# Regulators.net
KiCad netlist of a schematic drawn in Altium Designer
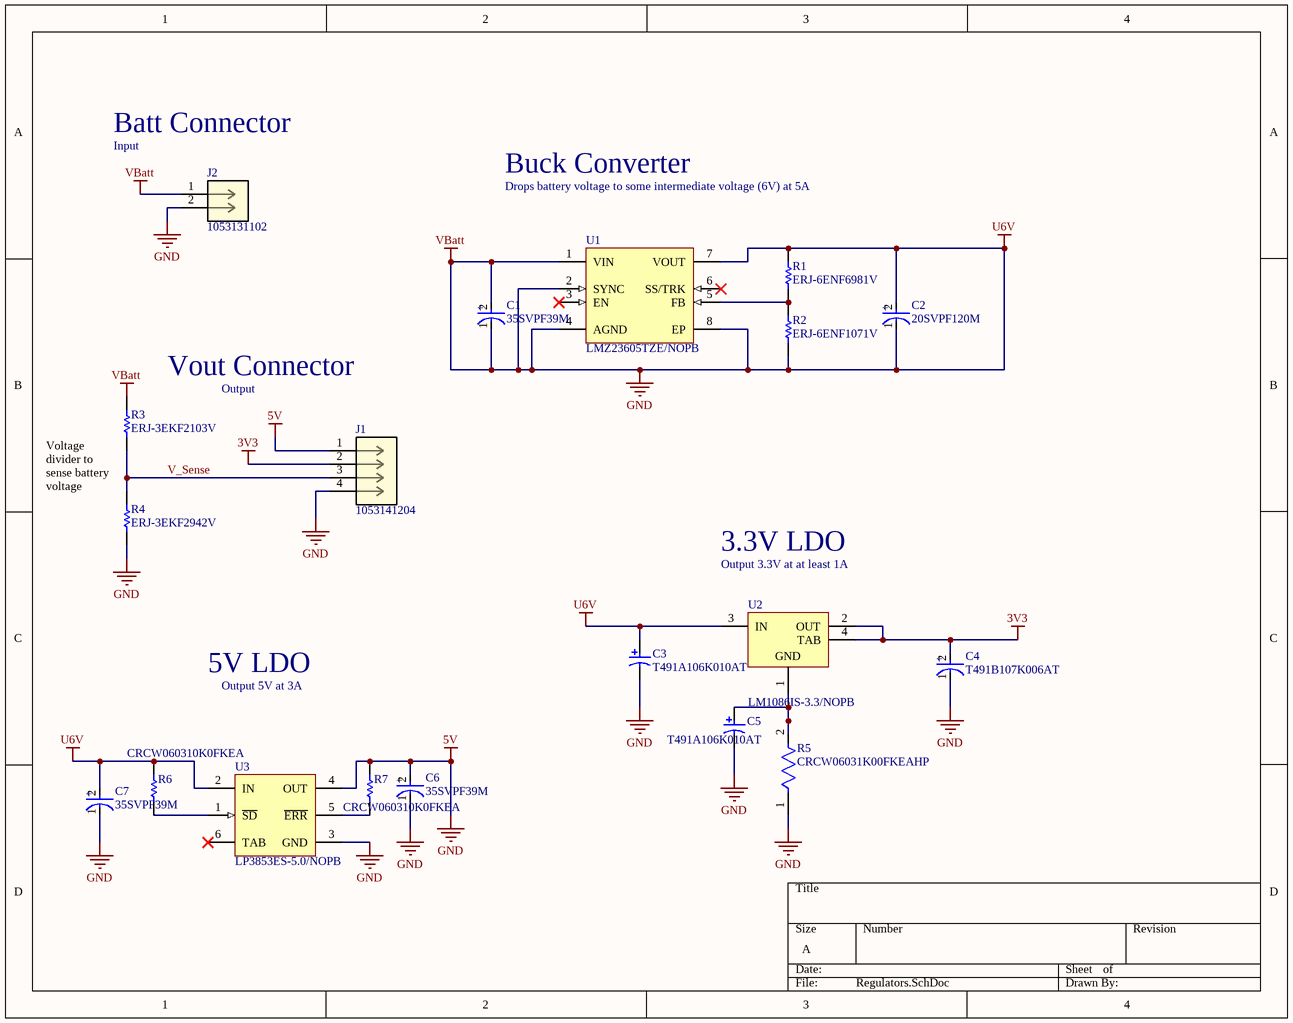
[diagram p0: Regulators.SchDoc]

(export (version "E")
  (design (tool "Eeschema 10.0.6"))
  (components
    (comp (ref "C1")
      (value "35SVPF39M")
      (footprint "FP-OS-CON-SMT-E7-MFG")
      (description "Conductive Polymer Aluminum Solid Capacitors (OS-CON) 39uF ±20% 35V RADIAL SMT 8x6.9mm")
      (fields (field (name "TOLERANCE") "20%") (field (name "VOLTAGE") "35V"))
      (libsource (lib "39uF Buck") (part "CMP-05428-001379-1"))
    )
    (comp (ref "C2")
      (value "20SVPF120M")
      (footprint "FP-OS-CON-SMT-C6-MFG")
      (description "Conductive Polymer Aluminum Solid Capacitors (OS-CON) 120uF ±20% 20V")
      (fields (field (name "TOLERANCE") "20%") (field (name "VOLTAGE") "20V"))
      (libsource (lib "120uF Buck") (part "CMP-05428-001333-1"))
    )
    (comp (ref "C3")
      (value "T491A106K010AT")
      (footprint "KEMT-A-3216-18-2_M")
      (description "Capacitor, Tantalum, 10 uF, +/- 10%, 10 V, -55 to 125 degC, 2-Pin SMD (1206), RoHS, Tape and Reel")
      (fields (field (name "TOLERANCE") "±10%") (field (name "MANUFACTURER") "Kemet"))
      (libsource (lib "10uF 3V3LDO") (part "CMP-2000-05172-1"))
    )
    (comp (ref "C4")
      (value "T491B107K006AT")
      (footprint "FP-T491B107K006AT-MFG")
      (description "CAP TANT 100UF 10% 6.3V 1411")
      (fields (field (name "VOLTAGE") "6.3V") (field (name "TOLERANCE") "10%"))
      (libsource (lib "100uF 3V3LDO") (part "CMP-03017-000031-1"))
    )
    (comp (ref "C5")
      (value "T491A106K010AT")
      (footprint "KEMT-A-3216-18-2_M")
      (description "Capacitor, Tantalum, 10 uF, +/- 10%, 10 V, -55 to 125 degC, 2-Pin SMD (1206), RoHS, Tape and Reel")
      (fields (field (name "TOLERANCE") "±10%") (field (name "MANUFACTURER") "Kemet"))
      (libsource (lib "10uF 3V3LDO") (part "CMP-2000-05172-1"))
    )
    (comp (ref "C6")
      (value "35SVPF39M")
      (footprint "FP-OS-CON-SMT-E7-MFG")
      (description "Conductive Polymer Aluminum Solid Capacitors (OS-CON) 39uF ±20% 35V RADIAL SMT 8x6.9mm")
      (fields (field (name "TOLERANCE") "20%") (field (name "VOLTAGE") "35V"))
      (libsource (lib "39uF Buck") (part "CMP-05428-001379-1"))
    )
    (comp (ref "C7")
      (value "35SVPF39M")
      (footprint "FP-OS-CON-SMT-E7-MFG")
      (description "Conductive Polymer Aluminum Solid Capacitors (OS-CON) 39uF ±20% 35V RADIAL SMT 8x6.9mm")
      (fields (field (name "TOLERANCE") "20%") (field (name "VOLTAGE") "35V"))
      (libsource (lib "39uF Buck") (part "CMP-05428-001379-1"))
    )
    (comp (ref "J1")
      (value "1053141204")
      (footprint "CON_1053141204")
      (description "No Description Available")
      (fields (field (name "COPYRIGHT") "Copyright (C) 2022 Ultra Librarian. All rights reserved."))
      (libsource (lib "tvc_lib_sch") (part "1053141204"))
    )
    (comp (ref "J2")
      (value "1053131102")
      (footprint "CON_1053131102")
      (description "No Description Available")
      (fields (field (name "COPYRIGHT") "Copyright (C) 2022 Ultra Librarian. All rights reserved."))
      (libsource (lib "tvc_lib_sch") (part "1053131102"))
    )
    (comp (ref "R1")
      (value "ERJ-6ENF6981V")
      (footprint "RESC2013X70X40NL20T20")
      (fields (field (name "MANUFACTURER") "Panasonic"))
      (libsource (lib "6.98kR Buck") (part "CMP-2001-00277-1"))
    )
    (comp (ref "R2")
      (value "ERJ-6ENF1071V")
      (footprint "RESC2013X70X40NL20T20")
      (fields (field (name "MANUFACTURER") "Panasonic"))
      (libsource (lib "1.07kR Buck") (part "CMP-2001-04388-1"))
    )
    (comp (ref "R3")
      (value "ERJ-3EKF2103V")
      (footprint "RESC1608X55X30NL15T15")
      (fields (field (name "MANUFACTURER") "Panasonic"))
      (libsource (lib "210kR VD") (part "CMP-2000-00329-1"))
    )
    (comp (ref "R4")
      (value "ERJ-3EKF2942V")
      (footprint "RESC1608X55X30NL15T15")
      (fields (field (name "MANUFACTURER") "Panasonic"))
      (libsource (lib "29.4kR VD") (part "CMP-2000-00409-1"))
    )
    (comp (ref "R5")
      (value "CRCW06031K00FKEAHP")
      (footprint "FP-CRCW0603-HPe3-IPC_B")
      (description "RES Thick Film, 1kΩ, 1%, 0.33W, 100ppm/°C, 0603")
      (fields (field (name "TOLERANCE") "1%"))
      (libsource (lib "1kR 3v3LDO") (part "CMP-2000-02970-2"))
    )
    (comp (ref "R6")
      (value "CRCW060310K0FKEA")
      (footprint "RESC1609X50X30LL8T20")
      (description "Chip Resistor, 10 KOhm, +/- 1%, 100 mW, -55 to 155 degC, 0603 (1608 Metric), RoHS, Tape and Reel")
      (fields (field (name "MANUFACTURER") "Vishay Semiconductor"))
      (libsource (lib "10kR 5LDO") (part "CMP-1666-00005-4"))
    )
    (comp (ref "R7")
      (value "CRCW060310K0FKEA")
      (footprint "RESC1609X50X30LL8T20")
      (description "Chip Resistor, 10 KOhm, +/- 1%, 100 mW, -55 to 155 degC, 0603 (1608 Metric), RoHS, Tape and Reel")
      (fields (field (name "MANUFACTURER") "Vishay Semiconductor"))
      (libsource (lib "10kR 5LDO") (part "CMP-1666-00005-4"))
    )
    (comp (ref "U1")
      (value "LMZ23605TZE/NOPB")
      (footprint "NDW0007A_V")
      (description "5A SIMPLE SWITCHER® Power Module with 36V Maximum Input Voltage, 7 pin TO-PMOD, 250 Reel")
      (fields (field (name "MANUFACTURER") "Texas Instruments"))
      (libsource (lib "25Vto6V 5A Buck") (part "CMP-0069-02071-2"))
    )
    (comp (ref "U2")
      (value "LM1086IS-3.3/NOPB")
      (footprint "KTT0003B_M")
      (description "1.5A Low Dropout Positive Regulators, 3-pin TO-263, Pb-Free")
      (fields (field (name "MANUFACTURER") "Texas Instruments"))
      (libsource (lib "3V3 1.5A LDO") (part "CMP-0062-00552-5"))
    )
    (comp (ref "U3")
      (value "LP3853ES-5.0/NOPB")
      (footprint "KTT0005B_N")
      (description "3A Fast Ultra Low Dropout Linear Regulator, 5-pin TO-263, Pb-Free")
      (fields (field (name "MANUFACTURER") "Texas Instruments"))
      (libsource (lib "6Vto5V5 LDO") (part "CMP-0062-00142-3"))
    )
  )
  (nets
    (net (code "1") (name "/V_Sense") (class "Default")
      (node (ref "J1") (pin "3") (pinfunction "3_3") (pintype "passive"))
      (node (ref "R3") (pin "1") (pinfunction "1_1") (pintype "passive"))
      (node (ref "R4") (pin "2") (pinfunction "2_2") (pintype "passive"))
    )
    (net (code "2") (name "3V3") (class "Default")
      (node (ref "C4") (pin "2") (pinfunction "A_2") (pintype "passive"))
      (node (ref "J1") (pin "2") (pinfunction "2_2") (pintype "passive"))
      (node (ref "U2") (pin "2") (pinfunction "OUT_2") (pintype "power_in"))
      (node (ref "U2") (pin "4") (pinfunction "TAB_4") (pintype "power_in"))
    )
    (net (code "3") (name "5V") (class "Default")
      (node (ref "C1") (pin "1") (pinfunction "C_1") (pintype "passive"))
      (node (ref "C1") (pin "2") (pinfunction "A_2") (pintype "passive"))
      (node (ref "C2") (pin "1") (pinfunction "C_1") (pintype "passive"))
      (node (ref "C2") (pin "2") (pinfunction "A_2") (pintype "passive"))
      (node (ref "C3") (pin "1") (pinfunction "1_1") (pintype "passive"))
      (node (ref "C3") (pin "2") (pinfunction "2_2") (pintype "passive"))
      (node (ref "C4") (pin "1") (pinfunction "C_1") (pintype "passive"))
      (node (ref "C5") (pin "2") (pinfunction "2_2") (pintype "passive"))
      (node (ref "C6") (pin "1") (pinfunction "C_1") (pintype "passive"))
      (node (ref "C6") (pin "2") (pinfunction "A_2") (pintype "passive"))
      (node (ref "C7") (pin "1") (pinfunction "C_1") (pintype "passive"))
      (node (ref "C7") (pin "2") (pinfunction "A_2") (pintype "passive"))
      (node (ref "J1") (pin "1") (pinfunction "1_1") (pintype "passive"))
      (node (ref "J1") (pin "4") (pinfunction "4_4") (pintype "passive"))
      (node (ref "J2") (pin "1") (pinfunction "1_1") (pintype "passive"))
      (node (ref "J2") (pin "2") (pinfunction "2_2") (pintype "passive"))
      (node (ref "R1") (pin "2") (pinfunction "2_2") (pintype "passive"))
      (node (ref "R2") (pin "1") (pinfunction "1_1") (pintype "passive"))
      (node (ref "R3") (pin "2") (pinfunction "2_2") (pintype "passive"))
      (node (ref "R4") (pin "1") (pinfunction "1_1") (pintype "passive"))
      (node (ref "R5") (pin "1") (pinfunction "1_1") (pintype "passive"))
      (node (ref "R6") (pin "2") (pinfunction "2_2") (pintype "passive"))
      (node (ref "R7") (pin "2") (pinfunction "2_2") (pintype "passive"))
      (node (ref "U1") (pin "1") (pinfunction "VIN_1") (pintype "power_in"))
      (node (ref "U1") (pin "2") (pinfunction "SYNC_2") (pintype "input"))
      (node (ref "U1") (pin "4") (pinfunction "AGND_4") (pintype "power_in"))
      (node (ref "U1") (pin "7") (pinfunction "VOUT_7") (pintype "power_in"))
      (node (ref "U1") (pin "8") (pinfunction "EP_8") (pintype "power_in"))
      (node (ref "U2") (pin "3") (pinfunction "IN_3") (pintype "power_in"))
      (node (ref "U3") (pin "2") (pinfunction "IN_2") (pintype "power_in"))
      (node (ref "U3") (pin "3") (pinfunction "GND_3") (pintype "power_in"))
      (node (ref "U3") (pin "4") (pinfunction "OUT_4") (pintype "power_in"))
    )
    (net (code "4") (name "Net-(U1-FB)") (class "Default")
      (node (ref "R1") (pin "1") (pinfunction "1_1") (pintype "passive"))
      (node (ref "R2") (pin "2") (pinfunction "2_2") (pintype "passive"))
      (node (ref "U1") (pin "5") (pinfunction "FB_5") (pintype "input"))
    )
    (net (code "5") (name "Net-(U2-GND)") (class "Default")
      (node (ref "C5") (pin "1") (pinfunction "1_1") (pintype "passive"))
      (node (ref "R5") (pin "2") (pinfunction "2_2") (pintype "passive"))
      (node (ref "U2") (pin "1") (pinfunction "GND_1") (pintype "power_in"))
    )
    (net (code "6") (name "Net-(U3-~{ERR})") (class "Default")
      (node (ref "R7") (pin "1") (pinfunction "1_1") (pintype "passive"))
      (node (ref "U3") (pin "5") (pinfunction "~{ERR}_5") (pintype "open_collector"))
    )
    (net (code "7") (name "Net-(U3-~{SD})") (class "Default")
      (node (ref "R6") (pin "1") (pinfunction "1_1") (pintype "passive"))
      (node (ref "U3") (pin "1") (pinfunction "~{SD}_1") (pintype "input"))
    )
    (net (code "8") (name "unconnected-(U1-EN-Pad3)") (class "Default")
      (node (ref "U1") (pin "3") (pinfunction "EN_3") (pintype "input+no_connect"))
    )
    (net (code "9") (name "unconnected-(U1-SS{slash}TRK-Pad6)") (class "Default")
      (node (ref "U1") (pin "6") (pinfunction "SS/TRK_6") (pintype "input+no_connect"))
    )
    (net (code "10") (name "unconnected-(U3-TAB-Pad6)") (class "Default")
      (node (ref "U3") (pin "6") (pinfunction "TAB_6") (pintype "power_in+no_connect"))
    )
  )
)
